# ProDoc_simpleCH552_typeA_sch_finished.net
KiCad netlist of a schematic drawn in EasyEDA Pro
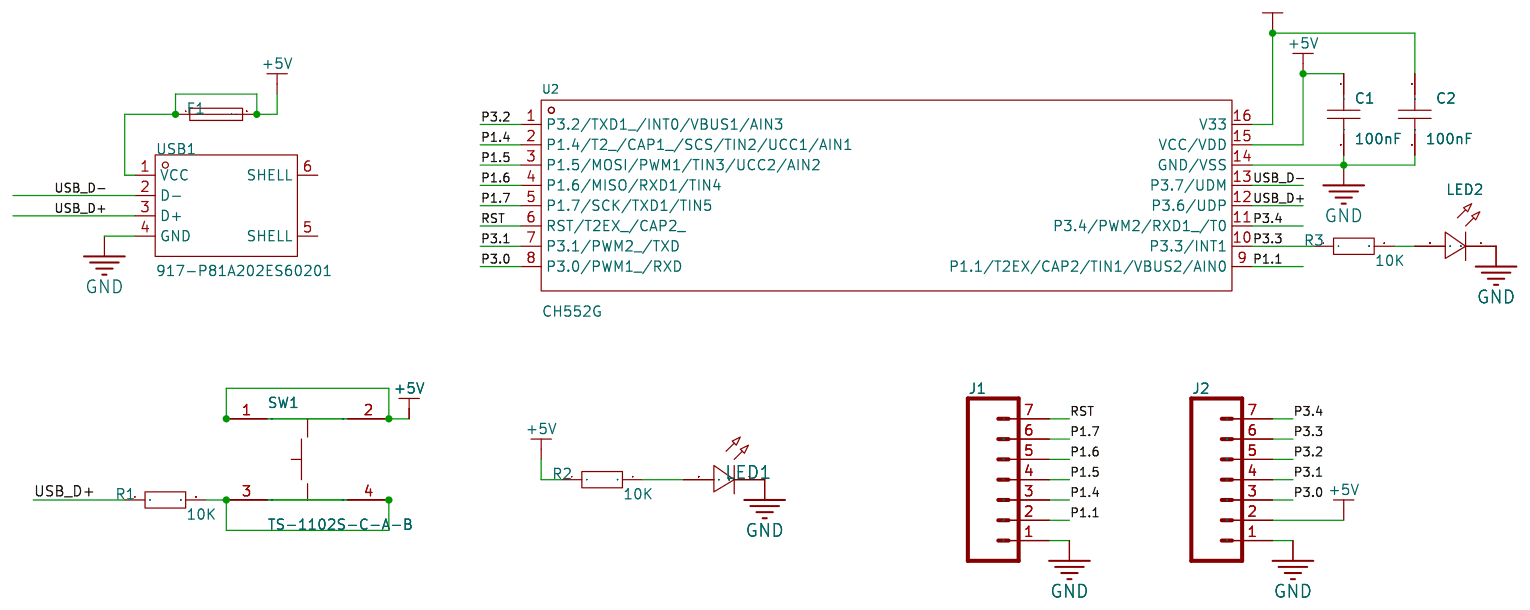
[diagram p0: schematic sheet]

(export (version "E")
  (design (tool "Eeschema 10.0.6"))
  (components
    (comp (ref "C1")
      (value "100nF")
      (footprint "easyedapro:C0805")
      (libsource (lib "easyedapro") (part "CAP"))
    )
    (comp (ref "C2")
      (value "100nF")
      (footprint "easyedapro:C0805")
      (libsource (lib "easyedapro") (part "CAP"))
    )
    (comp (ref "F1")
      (value "SF-1206S080-2")
      (footprint "easyedapro:F1206")
      (fields (field (name "Manufacturer") "BOURNS"))
      (libsource (lib "easyedapro") (part "SF-1206S080-2"))
    )
    (comp (ref "J1")
      (value "CONN_07NO_SILK")
      (footprint "easyedapro:1X07_NO_SILK")
      (libsource (lib "easyedapro") (part "SparkFun-Connectors_CONN_07_NO_SILK"))
    )
    (comp (ref "J2")
      (value "CONN_07NO_SILK")
      (footprint "easyedapro:1X07_NO_SILK")
      (libsource (lib "easyedapro") (part "SparkFun-Connectors_CONN_07_NO_SILK"))
    )
    (comp (ref "LED1")
      (value "~")
      (footprint "easyedapro:LED0805-RD_GREEN")
      (libsource (lib "easyedapro") (part "LED_R"))
    )
    (comp (ref "LED2")
      (value "~")
      (footprint "easyedapro:LED0805-RD_GREEN")
      (libsource (lib "easyedapro") (part "LED_G"))
    )
    (comp (ref "R1") (value "10K") (footprint "easyedapro:R0805") (libsource (lib "easyedapro") (part "Res")))
    (comp (ref "R2") (value "10K") (footprint "easyedapro:R0805") (libsource (lib "easyedapro") (part "Res")))
    (comp (ref "R3") (value "10K") (footprint "easyedapro:R0805") (libsource (lib "easyedapro") (part "Res")))
    (comp (ref "SW1")
      (value "TS-1102S-C-A-B")
      (footprint "easyedapro:KEY-SMD_4P-L6.0-W6.0-P4.50-LS8.6")
      (fields (field (name "Manufacturer") "XKB Connection(中国星坤)"))
      (libsource (lib "easyedapro") (part "TS-1102S-C-A-B"))
    )
    (comp (ref "U2")
      (value "CH552G")
      (footprint "easyedapro:SOP-16_L10.0-W3.9-P1.27-LS6.0-BL")
      (fields (field (name "Manufacturer") "WCH(南京沁恒)"))
      (libsource (lib "easyedapro") (part "CH552G"))
    )
    (comp (ref "USB1")
      (value "917-P81A202ES60201")
      (footprint "easyedapro:USB-A-SMD_917-P81A202ES60201")
      (fields (field (name "Manufacturer") "精拓金"))
      (libsource (lib "easyedapro") (part "917-P81A202ES60201"))
    )
  )
  (nets
    (net (code "1") (name "+5V") (class "Default")
      (node (ref "C1") (pin "1") (pinfunction "1_1") (pintype "input"))
      (node (ref "F1") (pin "1") (pinfunction "1_1") (pintype "unspecified"))
      (node (ref "F1") (pin "2") (pinfunction "2_2") (pintype "unspecified"))
      (node (ref "J2") (pin "2") (pinfunction "2_2") (pintype "unspecified"))
      (node (ref "R2") (pin "1") (pinfunction "1_1") (pintype "input"))
      (node (ref "SW1") (pin "1") (pinfunction "1_1") (pintype "unspecified"))
      (node (ref "SW1") (pin "2") (pinfunction "2_2") (pintype "unspecified"))
      (node (ref "U2") (pin "15") (pinfunction "VCC/VDD_15") (pintype "input"))
      (node (ref "USB1") (pin "1") (pinfunction "VCC_1") (pintype "unspecified"))
    )
    (net (code "2") (name "/P1.1") (class "Default")
      (node (ref "J1") (pin "2") (pinfunction "2_2") (pintype "unspecified"))
      (node (ref "U2") (pin "9") (pinfunction "P1.1/T2EX/CAP2/TIN1/VBUS2/AIN0_9") (pintype "input"))
    )
    (net (code "3") (name "/P1.4") (class "Default")
      (node (ref "J1") (pin "3") (pinfunction "3_3") (pintype "unspecified"))
      (node (ref "U2") (pin "2") (pinfunction "P1.4/T2_/CAP1_/SCS/TIN2/UCC1/AIN1_2") (pintype "input"))
    )
    (net (code "4") (name "/P1.5") (class "Default")
      (node (ref "J1") (pin "4") (pinfunction "4_4") (pintype "unspecified"))
      (node (ref "U2") (pin "3") (pinfunction "P1.5/MOSI/PWM1/TIN3/UCC2/AIN2_3") (pintype "input"))
    )
    (net (code "5") (name "/P1.6") (class "Default")
      (node (ref "J1") (pin "5") (pinfunction "5_5") (pintype "unspecified"))
      (node (ref "U2") (pin "4") (pinfunction "P1.6/MISO/RXD1/TIN4_4") (pintype "input"))
    )
    (net (code "6") (name "/P1.7") (class "Default")
      (node (ref "J1") (pin "6") (pinfunction "6_6") (pintype "unspecified"))
      (node (ref "U2") (pin "5") (pinfunction "P1.7/SCK/TXD1/TIN5_5") (pintype "input"))
    )
    (net (code "7") (name "/P3.0") (class "Default")
      (node (ref "J2") (pin "3") (pinfunction "3_3") (pintype "unspecified"))
      (node (ref "U2") (pin "8") (pinfunction "P3.0/PWM1_/RXD_8") (pintype "input"))
    )
    (net (code "8") (name "/P3.1") (class "Default")
      (node (ref "J2") (pin "4") (pinfunction "4_4") (pintype "unspecified"))
      (node (ref "U2") (pin "7") (pinfunction "P3.1/PWM2_/TXD_7") (pintype "input"))
    )
    (net (code "9") (name "/P3.2") (class "Default")
      (node (ref "J2") (pin "5") (pinfunction "5_5") (pintype "unspecified"))
      (node (ref "U2") (pin "1") (pinfunction "P3.2/TXD1_/INT0/VBUS1/AIN3_1") (pintype "input"))
    )
    (net (code "10") (name "/P3.3") (class "Default")
      (node (ref "J2") (pin "6") (pinfunction "6_6") (pintype "unspecified"))
      (node (ref "R3") (pin "1") (pinfunction "1_1") (pintype "input"))
      (node (ref "U2") (pin "10") (pinfunction "P3.3/INT1_10") (pintype "input"))
    )
    (net (code "11") (name "/P3.4") (class "Default")
      (node (ref "J2") (pin "7") (pinfunction "7_7") (pintype "unspecified"))
      (node (ref "U2") (pin "11") (pinfunction "P3.4/PWM2/RXD1_/T0_11") (pintype "input"))
    )
    (net (code "12") (name "/RST") (class "Default")
      (node (ref "J1") (pin "7") (pinfunction "7_7") (pintype "unspecified"))
      (node (ref "U2") (pin "6") (pinfunction "RST/T2EX_/CAP2__6") (pintype "input"))
    )
    (net (code "13") (name "/USB_D+") (class "Default")
      (node (ref "R1") (pin "1") (pinfunction "1_1") (pintype "input"))
      (node (ref "U2") (pin "12") (pinfunction "P3.6/UDP_12") (pintype "input"))
      (node (ref "USB1") (pin "3") (pinfunction "D+_3") (pintype "unspecified"))
    )
    (net (code "14") (name "/USB_D-") (class "Default")
      (node (ref "U2") (pin "13") (pinfunction "P3.7/UDM_13") (pintype "input"))
      (node (ref "USB1") (pin "2") (pinfunction "D-_2") (pintype "unspecified"))
    )
    (net (code "15") (name "3.3V") (class "Default")
      (node (ref "C2") (pin "1") (pinfunction "1_1") (pintype "input"))
      (node (ref "U2") (pin "16") (pinfunction "V33_16") (pintype "input"))
    )
    (net (code "16") (name "GND") (class "Default")
      (node (ref "C1") (pin "2") (pinfunction "2_2") (pintype "input"))
      (node (ref "C2") (pin "2") (pinfunction "2_2") (pintype "input"))
      (node (ref "J1") (pin "1") (pinfunction "1_1") (pintype "unspecified"))
      (node (ref "J2") (pin "1") (pinfunction "1_1") (pintype "unspecified"))
      (node (ref "LED1") (pin "1") (pinfunction "C_1") (pintype "input"))
      (node (ref "LED2") (pin "1") (pinfunction "C_1") (pintype "input"))
      (node (ref "U2") (pin "14") (pinfunction "GND/VSS_14") (pintype "input"))
      (node (ref "USB1") (pin "4") (pinfunction "GND_4") (pintype "unspecified"))
    )
    (net (code "17") (name "Net-(LED1-A)") (class "Default")
      (node (ref "LED1") (pin "2") (pinfunction "A_2") (pintype "input"))
      (node (ref "R2") (pin "2") (pinfunction "2_2") (pintype "input"))
    )
    (net (code "18") (name "Net-(LED2-A)") (class "Default")
      (node (ref "LED2") (pin "2") (pinfunction "A_2") (pintype "input"))
      (node (ref "R3") (pin "2") (pinfunction "2_2") (pintype "input"))
    )
    (net (code "19") (name "Net-(R1-Pad2)") (class "Default")
      (node (ref "R1") (pin "2") (pinfunction "2_2") (pintype "input"))
      (node (ref "SW1") (pin "3") (pinfunction "3_3") (pintype "unspecified"))
      (node (ref "SW1") (pin "4") (pinfunction "4_4") (pintype "unspecified"))
    )
    (net (code "20") (name "unconnected-(USB1-SHELL-Pad5)") (class "Default")
      (node (ref "USB1") (pin "5") (pinfunction "SHELL_5") (pintype "unspecified"))
    )
    (net (code "21") (name "unconnected-(USB1-SHELL-Pad6)") (class "Default")
      (node (ref "USB1") (pin "6") (pinfunction "SHELL_6") (pintype "unspecified"))
    )
  )
)
